# LineFollowTest.net
KiCad netlist of a schematic drawn in EAGLE
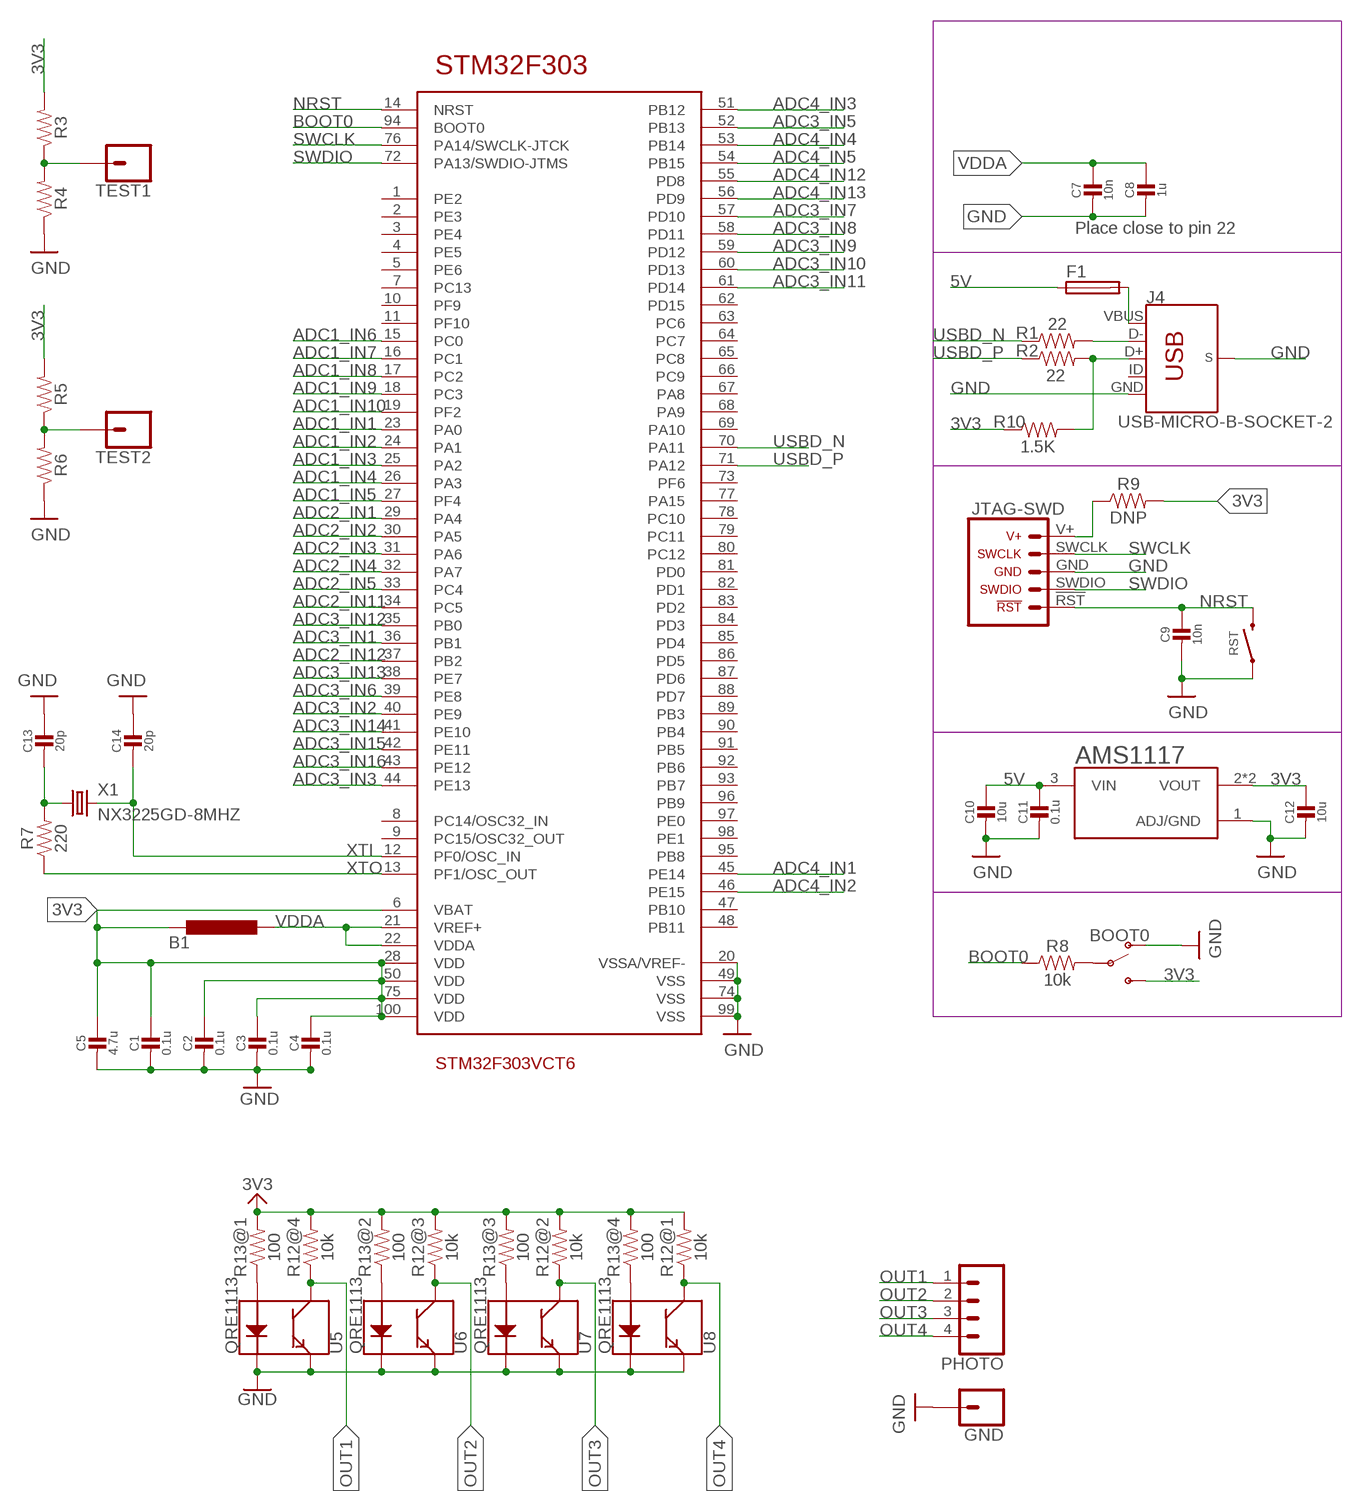
[diagram p0: schematic, sheet 1]
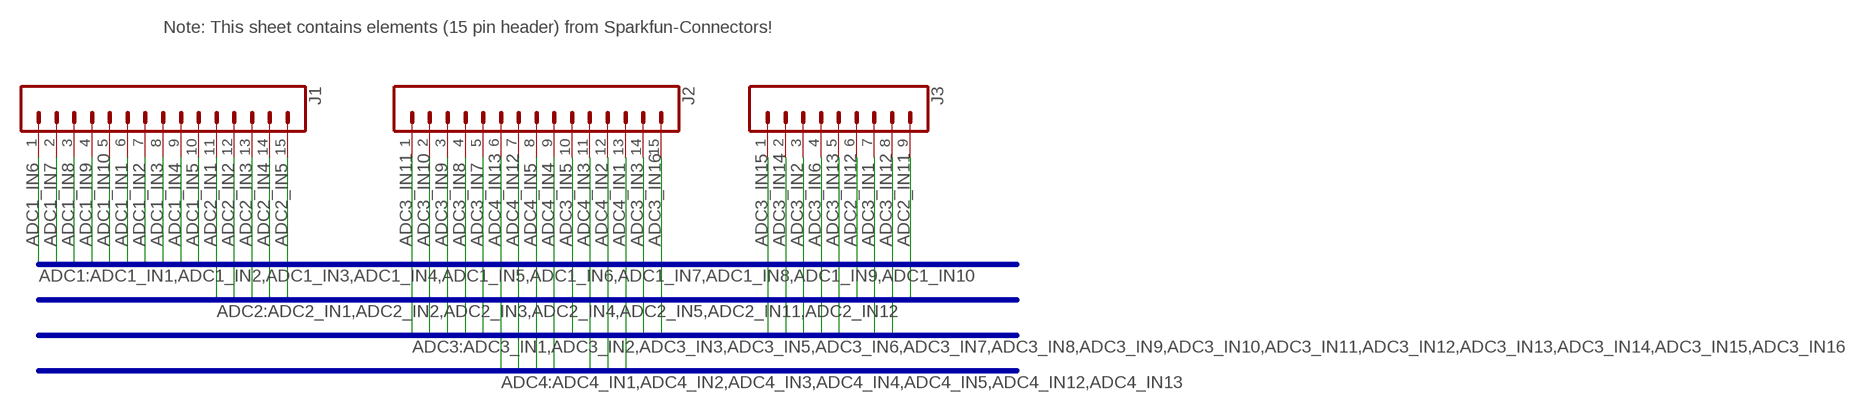
[diagram p1: schematic, sheet 2]
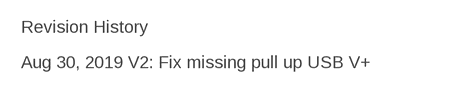
[diagram p2: schematic, sheet 3]

(export (version "E")
  (design (tool "Eeschema 10.0.6"))
  (components
    (comp (ref "J1")
      (value "CONN_15")
      (footprint "eagle-import:1X15")
      (libsource (lib "eagle-import") (part "CONN_15"))
    )
    (comp (ref "J2")
      (value "CONN_15")
      (footprint "eagle-import:1X15")
      (libsource (lib "eagle-import") (part "CONN_15"))
    )
    (comp (ref "J3")
      (value "CONN_09")
      (footprint "eagle-import:1X09")
      (libsource (lib "eagle-import") (part "CONN_09"))
    )
    (comp (ref "AMS1117")
      (value "3.3V")
      (footprint "eagle-import:SOT89")
      (libsource (lib "eagle-import") (part "VREG_AMS1117SMALL"))
    )
    (comp (ref "B1")
      (value "BEAD-0603")
      (footprint "eagle-import:0603")
      (libsource (lib "eagle-import") (part "BEAD-0603"))
    )
    (comp (ref "BOOT0")
      (value "SWITCH_SPDT_SLIDE")
      (footprint "eagle-import:SWITCH_SPDT_PTH_11.6X4.0MM")
      (libsource (lib "eagle-import") (part "SWITCH_SPDT_SLIDE"))
    )
    (comp (ref "C1")
      (value "0.1u")
      (footprint "eagle-import:CAP_0603")
      (libsource (lib "eagle-import") (part "CAP_CERAMIC_0603"))
    )
    (comp (ref "C2")
      (value "0.1u")
      (footprint "eagle-import:CAP_0603")
      (libsource (lib "eagle-import") (part "CAP_CERAMIC_0603"))
    )
    (comp (ref "C3")
      (value "0.1u")
      (footprint "eagle-import:CAP_0603")
      (libsource (lib "eagle-import") (part "CAP_CERAMIC_0603"))
    )
    (comp (ref "C4")
      (value "0.1u")
      (footprint "eagle-import:CAP_0603")
      (libsource (lib "eagle-import") (part "CAP_CERAMIC_0603"))
    )
    (comp (ref "C5")
      (value "4.7u")
      (footprint "eagle-import:CAP_0603")
      (libsource (lib "eagle-import") (part "CAP_CERAMIC_0603"))
    )
    (comp (ref "C7")
      (value "10n")
      (footprint "eagle-import:CAP_0603")
      (libsource (lib "eagle-import") (part "CAP_CERAMIC_0603"))
    )
    (comp (ref "C8")
      (value "1u")
      (footprint "eagle-import:CAP_0603")
      (libsource (lib "eagle-import") (part "CAP_CERAMIC_0603"))
    )
    (comp (ref "C9")
      (value "10n")
      (footprint "eagle-import:CAP_0603")
      (libsource (lib "eagle-import") (part "CAP_CERAMIC_0603"))
    )
    (comp (ref "C10")
      (value "10u")
      (footprint "eagle-import:CAP_0603")
      (libsource (lib "eagle-import") (part "CAP_CERAMIC_0603"))
    )
    (comp (ref "C11")
      (value "0.1u")
      (footprint "eagle-import:CAP_0603")
      (libsource (lib "eagle-import") (part "CAP_CERAMIC_0603"))
    )
    (comp (ref "C12")
      (value "10u")
      (footprint "eagle-import:CAP_0603")
      (libsource (lib "eagle-import") (part "CAP_CERAMIC_0603"))
    )
    (comp (ref "C13")
      (value "20p")
      (footprint "eagle-import:CAP_0603")
      (libsource (lib "eagle-import") (part "CAP_CERAMIC_0603"))
    )
    (comp (ref "C14")
      (value "20p")
      (footprint "eagle-import:CAP_0603")
      (libsource (lib "eagle-import") (part "CAP_CERAMIC_0603"))
    )
    (comp (ref "F1")
      (value "FUSE-1206")
      (footprint "eagle-import:1206")
      (libsource (lib "eagle-import") (part "FUSE-1206"))
    )
    (comp (ref "GND")
      (value "THD_01")
      (footprint "eagle-import:1X01")
      (libsource (lib "eagle-import") (part "THD_01"))
    )
    (comp (ref "J4")
      (value "USB-MICRO-B-SOCKET-2")
      (footprint "eagle-import:USB-MICRO-B-SOCKET-2")
      (libsource (lib "eagle-import") (part "USB-MICRO-B-SOCKET-2"))
    )
    (comp (ref "PHOTO")
      (value "CONN_04PTH")
      (footprint "eagle-import:1X04")
      (libsource (lib "eagle-import") (part "CONN_04PTH"))
    )
    (comp (ref "R1")
      (value "22")
      (footprint "eagle-import:0603")
      (libsource (lib "eagle-import") (part "RESISTOR0603"))
    )
    (comp (ref "R2")
      (value "22")
      (footprint "eagle-import:0603")
      (libsource (lib "eagle-import") (part "RESISTOR0603"))
    )
    (comp (ref "R3")
      (value "RESISTOR0603")
      (footprint "eagle-import:0603")
      (libsource (lib "eagle-import") (part "RESISTOR0603"))
    )
    (comp (ref "R4")
      (value "RESISTOR0603")
      (footprint "eagle-import:0603")
      (libsource (lib "eagle-import") (part "RESISTOR0603"))
    )
    (comp (ref "R5")
      (value "RESISTOR0603")
      (footprint "eagle-import:0603")
      (libsource (lib "eagle-import") (part "RESISTOR0603"))
    )
    (comp (ref "R6")
      (value "RESISTOR0603")
      (footprint "eagle-import:0603")
      (libsource (lib "eagle-import") (part "RESISTOR0603"))
    )
    (comp (ref "R7")
      (value "220")
      (footprint "eagle-import:0603")
      (libsource (lib "eagle-import") (part "RESISTOR0603"))
    )
    (comp (ref "R8")
      (value "10k")
      (footprint "eagle-import:0603")
      (libsource (lib "eagle-import") (part "RESISTOR0603"))
    )
    (comp (ref "R9")
      (value "DNP")
      (footprint "eagle-import:0603")
      (libsource (lib "eagle-import") (part "RESISTOR0603"))
    )
    (comp (ref "R10")
      (value "1.5K")
      (footprint "eagle-import:0603")
      (libsource (lib "eagle-import") (part "RESISTOR0603"))
    )
    (comp (ref "R12")
      (value "10k")
      (footprint "eagle-import:RESCAF80P320X160X60-8N")
      (libsource (lib "eagle-import") (part "RESISTOR_ARRAY_1206_SEPARATE"))
    )
    (comp (ref "R13")
      (value "100")
      (footprint "eagle-import:RESCAF80P320X160X60-8N")
      (libsource (lib "eagle-import") (part "RESISTOR_ARRAY_1206_SEPARATE"))
    )
    (comp (ref "RST")
      (value "PUSHBUTTON")
      (footprint "eagle-import:TACTILE_SWITCH_SMD_6.0X3.5MM")
      (libsource (lib "eagle-import") (part "PUSHBUTTON"))
    )
    (comp (ref "STM32F303")
      (value "STM32F303VCT6")
      (footprint "eagle-import:LQFP-100")
      (libsource (lib "eagle-import") (part "STM32F303VCT6"))
    )
    (comp (ref "TEST1")
      (value "THD_01")
      (footprint "eagle-import:1X01")
      (libsource (lib "eagle-import") (part "THD_01"))
    )
    (comp (ref "TEST2")
      (value "THD_01")
      (footprint "eagle-import:1X01")
      (libsource (lib "eagle-import") (part "THD_01"))
    )
    (comp (ref "U$3")
      (value "JTAG-SWD")
      (footprint "eagle-import:JTAG_SWD")
      (libsource (lib "eagle-import") (part "JTAG-SWD"))
    )
    (comp (ref "U5")
      (value "QRE1113")
      (footprint "eagle-import:QRE1113-W")
      (libsource (lib "eagle-import") (part "QRE1113SMD-W"))
    )
    (comp (ref "U6")
      (value "QRE1113")
      (footprint "eagle-import:QRE1113-W")
      (libsource (lib "eagle-import") (part "QRE1113SMD-W"))
    )
    (comp (ref "U7")
      (value "QRE1113")
      (footprint "eagle-import:QRE1113-W")
      (libsource (lib "eagle-import") (part "QRE1113SMD-W"))
    )
    (comp (ref "U8")
      (value "QRE1113")
      (footprint "eagle-import:QRE1113-W")
      (libsource (lib "eagle-import") (part "QRE1113SMD-W"))
    )
    (comp (ref "X1")
      (value "NX3225GD-8MHZ")
      (footprint "eagle-import:XTAL-SMD-3225")
      (libsource (lib "eagle-import") (part "XTAL-SMD-3225"))
    )
  )
  (nets
    (net (code "9") (name "3V3") (class "Default")
      (node (ref "AMS1117") (pin "2") (pinfunction "VOUT_2") (pintype "output"))
      (node (ref "AMS1117") (pin "2@1") (pinfunction "VOUT_2@1") (pintype "output"))
      (node (ref "B1") (pin "1") (pinfunction "P$1_1") (pintype "passive"))
      (node (ref "BOOT0") (pin "3") (pinfunction "S_3") (pintype "passive"))
      (node (ref "C1") (pin "1") (pinfunction "1_1") (pintype "passive"))
      (node (ref "C12") (pin "1") (pinfunction "1_1") (pintype "passive"))
      (node (ref "C2") (pin "1") (pinfunction "1_1") (pintype "passive"))
      (node (ref "C3") (pin "1") (pinfunction "1_1") (pintype "passive"))
      (node (ref "C4") (pin "1") (pinfunction "1_1") (pintype "passive"))
      (node (ref "C5") (pin "1") (pinfunction "1_1") (pintype "passive"))
      (node (ref "R10") (pin "1") (pinfunction "1_1") (pintype "passive"))
      (node (ref "R12") (pin "5") (pinfunction "2_5") (pintype "passive"))
      (node (ref "R12") (pin "6") (pinfunction "2_6") (pintype "passive"))
      (node (ref "R12") (pin "7") (pinfunction "2_7") (pintype "passive"))
      (node (ref "R12") (pin "8") (pinfunction "2_8") (pintype "passive"))
      (node (ref "R13") (pin "5") (pinfunction "2_5") (pintype "passive"))
      (node (ref "R13") (pin "6") (pinfunction "2_6") (pintype "passive"))
      (node (ref "R13") (pin "7") (pinfunction "2_7") (pintype "passive"))
      (node (ref "R13") (pin "8") (pinfunction "2_8") (pintype "passive"))
      (node (ref "R3") (pin "2") (pinfunction "2_2") (pintype "passive"))
      (node (ref "R5") (pin "2") (pinfunction "2_2") (pintype "passive"))
      (node (ref "R9") (pin "2") (pinfunction "2_2") (pintype "passive"))
      (node (ref "STM32F303") (pin "100") (pinfunction "VDD_100") (pintype "bidirectional"))
      (node (ref "STM32F303") (pin "28") (pinfunction "VDD_28") (pintype "bidirectional"))
      (node (ref "STM32F303") (pin "50") (pinfunction "VDD_50") (pintype "bidirectional"))
      (node (ref "STM32F303") (pin "6") (pinfunction "VBAT_6") (pintype "bidirectional"))
      (node (ref "STM32F303") (pin "75") (pinfunction "VDD_75") (pintype "bidirectional"))
    )
    (net (code "10") (name "5V") (class "Default")
      (node (ref "AMS1117") (pin "3") (pinfunction "VIN_3") (pintype "input"))
      (node (ref "C10") (pin "1") (pinfunction "1_1") (pintype "passive"))
      (node (ref "C11") (pin "1") (pinfunction "1_1") (pintype "passive"))
      (node (ref "F1") (pin "1") (pinfunction "1_1") (pintype "passive"))
    )
    (net (code "11") (name "ADC1_IN1") (class "Default")
      (node (ref "J1") (pin "6") (pinfunction "6_6") (pintype "passive"))
      (node (ref "STM32F303") (pin "23") (pinfunction "PA0_23") (pintype "bidirectional"))
    )
    (net (code "12") (name "ADC1_IN2") (class "Default")
      (node (ref "J1") (pin "7") (pinfunction "7_7") (pintype "passive"))
      (node (ref "STM32F303") (pin "24") (pinfunction "PA1_24") (pintype "bidirectional"))
    )
    (net (code "13") (name "ADC1_IN3") (class "Default")
      (node (ref "J1") (pin "8") (pinfunction "8_8") (pintype "passive"))
      (node (ref "STM32F303") (pin "25") (pinfunction "PA2_25") (pintype "bidirectional"))
    )
    (net (code "14") (name "ADC1_IN4") (class "Default")
      (node (ref "J1") (pin "9") (pinfunction "9_9") (pintype "passive"))
      (node (ref "STM32F303") (pin "26") (pinfunction "PA3_26") (pintype "bidirectional"))
    )
    (net (code "15") (name "ADC1_IN5") (class "Default")
      (node (ref "J1") (pin "10") (pinfunction "10_10") (pintype "passive"))
      (node (ref "STM32F303") (pin "27") (pinfunction "PF4_27") (pintype "bidirectional"))
    )
    (net (code "16") (name "ADC1_IN6") (class "Default")
      (node (ref "J1") (pin "1") (pinfunction "1_1") (pintype "passive"))
      (node (ref "STM32F303") (pin "15") (pinfunction "PC0_15") (pintype "bidirectional"))
    )
    (net (code "17") (name "ADC1_IN7") (class "Default")
      (node (ref "J1") (pin "2") (pinfunction "2_2") (pintype "passive"))
      (node (ref "STM32F303") (pin "16") (pinfunction "PC1_16") (pintype "bidirectional"))
    )
    (net (code "18") (name "ADC1_IN8") (class "Default")
      (node (ref "J1") (pin "3") (pinfunction "3_3") (pintype "passive"))
      (node (ref "STM32F303") (pin "17") (pinfunction "PC2_17") (pintype "bidirectional"))
    )
    (net (code "19") (name "ADC1_IN9") (class "Default")
      (node (ref "J1") (pin "4") (pinfunction "4_4") (pintype "passive"))
      (node (ref "STM32F303") (pin "18") (pinfunction "PC3_18") (pintype "bidirectional"))
    )
    (net (code "20") (name "ADC1_IN10") (class "Default")
      (node (ref "J1") (pin "5") (pinfunction "5_5") (pintype "passive"))
      (node (ref "STM32F303") (pin "19") (pinfunction "PF2_19") (pintype "bidirectional"))
    )
    (net (code "21") (name "ADC2_IN1") (class "Default")
      (node (ref "J1") (pin "11") (pinfunction "11_11") (pintype "passive"))
      (node (ref "STM32F303") (pin "29") (pinfunction "PA4_29") (pintype "bidirectional"))
    )
    (net (code "22") (name "ADC2_IN2") (class "Default")
      (node (ref "J1") (pin "12") (pinfunction "12_12") (pintype "passive"))
      (node (ref "STM32F303") (pin "30") (pinfunction "PA5_30") (pintype "bidirectional"))
    )
    (net (code "23") (name "ADC2_IN3") (class "Default")
      (node (ref "J1") (pin "13") (pinfunction "13_13") (pintype "passive"))
      (node (ref "STM32F303") (pin "31") (pinfunction "PA6_31") (pintype "bidirectional"))
    )
    (net (code "24") (name "ADC2_IN4") (class "Default")
      (node (ref "J1") (pin "14") (pinfunction "14_14") (pintype "passive"))
      (node (ref "STM32F303") (pin "32") (pinfunction "PA7_32") (pintype "bidirectional"))
    )
    (net (code "25") (name "ADC2_IN5") (class "Default")
      (node (ref "J1") (pin "15") (pinfunction "15_15") (pintype "passive"))
      (node (ref "STM32F303") (pin "33") (pinfunction "PC4_33") (pintype "bidirectional"))
    )
    (net (code "26") (name "ADC2_IN11") (class "Default")
      (node (ref "J3") (pin "9") (pinfunction "9_9") (pintype "passive"))
      (node (ref "STM32F303") (pin "34") (pinfunction "PC5_34") (pintype "bidirectional"))
    )
    (net (code "27") (name "ADC2_IN12") (class "Default")
      (node (ref "J3") (pin "6") (pinfunction "6_6") (pintype "passive"))
      (node (ref "STM32F303") (pin "37") (pinfunction "PB2_37") (pintype "bidirectional"))
    )
    (net (code "28") (name "ADC3_IN1") (class "Default")
      (node (ref "J3") (pin "7") (pinfunction "7_7") (pintype "passive"))
      (node (ref "STM32F303") (pin "36") (pinfunction "PB1_36") (pintype "bidirectional"))
    )
    (net (code "29") (name "ADC3_IN2") (class "Default")
      (node (ref "J3") (pin "3") (pinfunction "3_3") (pintype "passive"))
      (node (ref "STM32F303") (pin "40") (pinfunction "PE9_40") (pintype "bidirectional"))
    )
    (net (code "30") (name "ADC3_IN3") (class "Default")
      (node (ref "J2") (pin "14") (pinfunction "14_14") (pintype "passive"))
      (node (ref "STM32F303") (pin "44") (pinfunction "PE13_44") (pintype "bidirectional"))
    )
    (net (code "31") (name "ADC3_IN5") (class "Default")
      (node (ref "J2") (pin "10") (pinfunction "10_10") (pintype "passive"))
      (node (ref "STM32F303") (pin "52") (pinfunction "PB13_52") (pintype "bidirectional"))
    )
    (net (code "32") (name "ADC3_IN6") (class "Default")
      (node (ref "J3") (pin "4") (pinfunction "4_4") (pintype "passive"))
      (node (ref "STM32F303") (pin "39") (pinfunction "PE8_39") (pintype "bidirectional"))
    )
    (net (code "33") (name "ADC3_IN7") (class "Default")
      (node (ref "J2") (pin "5") (pinfunction "5_5") (pintype "passive"))
      (node (ref "STM32F303") (pin "57") (pinfunction "PD10_57") (pintype "bidirectional"))
    )
    (net (code "34") (name "ADC3_IN8") (class "Default")
      (node (ref "J2") (pin "4") (pinfunction "4_4") (pintype "passive"))
      (node (ref "STM32F303") (pin "58") (pinfunction "PD11_58") (pintype "bidirectional"))
    )
    (net (code "35") (name "ADC3_IN9") (class "Default")
      (node (ref "J2") (pin "3") (pinfunction "3_3") (pintype "passive"))
      (node (ref "STM32F303") (pin "59") (pinfunction "PD12_59") (pintype "bidirectional"))
    )
    (net (code "36") (name "ADC3_IN10") (class "Default")
      (node (ref "J2") (pin "2") (pinfunction "2_2") (pintype "passive"))
      (node (ref "STM32F303") (pin "60") (pinfunction "PD13_60") (pintype "bidirectional"))
    )
    (net (code "37") (name "ADC3_IN11") (class "Default")
      (node (ref "J2") (pin "1") (pinfunction "1_1") (pintype "passive"))
      (node (ref "STM32F303") (pin "61") (pinfunction "PD14_61") (pintype "bidirectional"))
    )
    (net (code "38") (name "ADC3_IN12") (class "Default")
      (node (ref "J3") (pin "8") (pinfunction "8_8") (pintype "passive"))
      (node (ref "STM32F303") (pin "35") (pinfunction "PB0_35") (pintype "bidirectional"))
    )
    (net (code "39") (name "ADC3_IN13") (class "Default")
      (node (ref "J3") (pin "5") (pinfunction "5_5") (pintype "passive"))
      (node (ref "STM32F303") (pin "38") (pinfunction "PE7_38") (pintype "bidirectional"))
    )
    (net (code "40") (name "ADC3_IN14") (class "Default")
      (node (ref "J3") (pin "2") (pinfunction "2_2") (pintype "passive"))
      (node (ref "STM32F303") (pin "41") (pinfunction "PE10_41") (pintype "bidirectional"))
    )
    (net (code "41") (name "ADC3_IN15") (class "Default")
      (node (ref "J3") (pin "1") (pinfunction "1_1") (pintype "passive"))
      (node (ref "STM32F303") (pin "42") (pinfunction "PE11_42") (pintype "bidirectional"))
    )
    (net (code "42") (name "ADC3_IN16") (class "Default")
      (node (ref "J2") (pin "15") (pinfunction "15_15") (pintype "passive"))
      (node (ref "STM32F303") (pin "43") (pinfunction "PE12_43") (pintype "bidirectional"))
    )
    (net (code "43") (name "ADC4_IN1") (class "Default")
      (node (ref "J2") (pin "13") (pinfunction "13_13") (pintype "passive"))
      (node (ref "STM32F303") (pin "45") (pinfunction "PE14_45") (pintype "bidirectional"))
    )
    (net (code "44") (name "ADC4_IN2") (class "Default")
      (node (ref "J2") (pin "12") (pinfunction "12_12") (pintype "passive"))
      (node (ref "STM32F303") (pin "46") (pinfunction "PE15_46") (pintype "bidirectional"))
    )
    (net (code "45") (name "ADC4_IN3") (class "Default")
      (node (ref "J2") (pin "11") (pinfunction "11_11") (pintype "passive"))
      (node (ref "STM32F303") (pin "51") (pinfunction "PB12_51") (pintype "bidirectional"))
    )
    (net (code "46") (name "ADC4_IN4") (class "Default")
      (node (ref "J2") (pin "9") (pinfunction "9_9") (pintype "passive"))
      (node (ref "STM32F303") (pin "53") (pinfunction "PB14_53") (pintype "bidirectional"))
    )
    (net (code "47") (name "ADC4_IN5") (class "Default")
      (node (ref "J2") (pin "8") (pinfunction "8_8") (pintype "passive"))
      (node (ref "STM32F303") (pin "54") (pinfunction "PB15_54") (pintype "bidirectional"))
    )
    (net (code "48") (name "ADC4_IN12") (class "Default")
      (node (ref "J2") (pin "7") (pinfunction "7_7") (pintype "passive"))
      (node (ref "STM32F303") (pin "55") (pinfunction "PD8_55") (pintype "bidirectional"))
    )
    (net (code "49") (name "ADC4_IN13") (class "Default")
      (node (ref "J2") (pin "6") (pinfunction "6_6") (pintype "passive"))
      (node (ref "STM32F303") (pin "56") (pinfunction "PD9_56") (pintype "bidirectional"))
    )
    (net (code "50") (name "BOOT0") (class "Default")
      (node (ref "R8") (pin "1") (pinfunction "1_1") (pintype "passive"))
      (node (ref "STM32F303") (pin "94") (pinfunction "BOOT0_94") (pintype "bidirectional"))
    )
    (net (code "51") (name "GND") (class "Default")
      (node (ref "AMS1117") (pin "1") (pinfunction "ADJ/GND_1") (pintype "power_in"))
      (node (ref "BOOT0") (pin "1") (pinfunction "O_1") (pintype "passive"))
      (node (ref "C1") (pin "2") (pinfunction "2_2") (pintype "passive"))
      (node (ref "C10") (pin "2") (pinfunction "2_2") (pintype "passive"))
      (node (ref "C11") (pin "2") (pinfunction "2_2") (pintype "passive"))
      (node (ref "C12") (pin "2") (pinfunction "2_2") (pintype "passive"))
      (node (ref "C13") (pin "1") (pinfunction "1_1") (pintype "passive"))
      (node (ref "C14") (pin "1") (pinfunction "1_1") (pintype "passive"))
      (node (ref "C2") (pin "2") (pinfunction "2_2") (pintype "passive"))
      (node (ref "C3") (pin "2") (pinfunction "2_2") (pintype "passive"))
      (node (ref "C4") (pin "2") (pinfunction "2_2") (pintype "passive"))
      (node (ref "C5") (pin "2") (pinfunction "2_2") (pintype "passive"))
      (node (ref "C7") (pin "2") (pinfunction "2_2") (pintype "passive"))
      (node (ref "C8") (pin "2") (pinfunction "2_2") (pintype "passive"))
      (node (ref "C9") (pin "2") (pinfunction "2_2") (pintype "passive"))
      (node (ref "GND") (pin "1") (pinfunction "1_1") (pintype "passive"))
      (node (ref "J4") (pin "GND") (pinfunction "GND_GND") (pintype "power_in"))
      (node (ref "J4") (pin "S1") (pinfunction "SHIELD_S1") (pintype "bidirectional"))
      (node (ref "J4") (pin "S2") (pinfunction "SHIELD_S2") (pintype "bidirectional"))
      (node (ref "J4") (pin "S3") (pinfunction "SHIELD_S3") (pintype "bidirectional"))
      (node (ref "J4") (pin "S4") (pinfunction "SHIELD_S4") (pintype "bidirectional"))
      (node (ref "J4") (pin "S5") (pinfunction "SHIELD_S5") (pintype "bidirectional"))
      (node (ref "R4") (pin "1") (pinfunction "1_1") (pintype "passive"))
      (node (ref "R6") (pin "1") (pinfunction "1_1") (pintype "passive"))
      (node (ref "RST") (pin "1") (pinfunction "1_1") (pintype "passive"))
      (node (ref "STM32F303") (pin "20") (pinfunction "VSSA/VREF-_20") (pintype "bidirectional"))
      (node (ref "STM32F303") (pin "49") (pinfunction "VSS_49") (pintype "bidirectional"))
      (node (ref "STM32F303") (pin "74") (pinfunction "VSS_74") (pintype "bidirectional"))
      (node (ref "STM32F303") (pin "99") (pinfunction "VSS_99") (pintype "bidirectional"))
      (node (ref "U$3") (pin "GND") (pinfunction "GND_GND") (pintype "passive"))
      (node (ref "U5") (pin "2") (pinfunction "K_2") (pintype "bidirectional"))
      (node (ref "U5") (pin "4") (pinfunction "E_4") (pintype "bidirectional"))
      (node (ref "U6") (pin "2") (pinfunction "K_2") (pintype "bidirectional"))
      (node (ref "U6") (pin "4") (pinfunction "E_4") (pintype "bidirectional"))
      (node (ref "U7") (pin "2") (pinfunction "K_2") (pintype "bidirectional"))
      (node (ref "U7") (pin "4") (pinfunction "E_4") (pintype "bidirectional"))
      (node (ref "U8") (pin "2") (pinfunction "K_2") (pintype "bidirectional"))
      (node (ref "U8") (pin "4") (pinfunction "E_4") (pintype "bidirectional"))
    )
    (net (code "52") (name "NRST") (class "Default")
      (node (ref "C9") (pin "1") (pinfunction "1_1") (pintype "passive"))
      (node (ref "RST") (pin "2") (pinfunction "2_2") (pintype "passive"))
      (node (ref "STM32F303") (pin "14") (pinfunction "NRST_14") (pintype "bidirectional"))
      (node (ref "U$3") (pin "!RST") (pinfunction "~{RST}_!RST") (pintype "passive"))
    )
    (net (code "53") (name "Net-(BOOT0-P)") (class "Default")
      (node (ref "BOOT0") (pin "2") (pinfunction "P_2") (pintype "passive"))
      (node (ref "R8") (pin "2") (pinfunction "2_2") (pintype "passive"))
    )
    (net (code "54") (name "Net-(C13-Pad2)") (class "Default")
      (node (ref "C13") (pin "2") (pinfunction "2_2") (pintype "passive"))
      (node (ref "R7") (pin "2") (pinfunction "2_2") (pintype "passive"))
      (node (ref "X1") (pin "1") (pinfunction "1_1") (pintype "passive"))
    )
    (net (code "55") (name "Net-(F1-Pad2)") (class "Default")
      (node (ref "F1") (pin "2") (pinfunction "2_2") (pintype "passive"))
      (node (ref "J4") (pin "VBUS") (pinfunction "VBUS_VBUS") (pintype "power_in"))
    )
    (net (code "56") (name "Net-(J4-PadD+)") (class "Default")
      (node (ref "J4") (pin "D+") (pinfunction "D+_D+") (pintype "bidirectional"))
      (node (ref "R10") (pin "2") (pinfunction "2_2") (pintype "passive"))
      (node (ref "R2") (pin "2") (pinfunction "2_2") (pintype "passive"))
    )
    (net (code "57") (name "Net-(J4-PadD-)") (class "Default")
      (node (ref "J4") (pin "D-") (pinfunction "D-_D-") (pintype "bidirectional"))
      (node (ref "R1") (pin "2") (pinfunction "2_2") (pintype "passive"))
    )
    (net (code "58") (name "Net-(R3-Pad1)") (class "Default")
      (node (ref "R3") (pin "1") (pinfunction "1_1") (pintype "passive"))
      (node (ref "R4") (pin "2") (pinfunction "2_2") (pintype "passive"))
      (node (ref "TEST1") (pin "1") (pinfunction "1_1") (pintype "passive"))
    )
    (net (code "59") (name "Net-(R5-Pad1)") (class "Default")
      (node (ref "R5") (pin "1") (pinfunction "1_1") (pintype "passive"))
      (node (ref "R6") (pin "2") (pinfunction "2_2") (pintype "passive"))
      (node (ref "TEST2") (pin "1") (pinfunction "1_1") (pintype "passive"))
    )
    (net (code "60") (name "Net-(R9-Pad1)") (class "Default")
      (node (ref "R9") (pin "1") (pinfunction "1_1") (pintype "passive"))
      (node (ref "U$3") (pin "V+") (pinfunction "V+_V+") (pintype "passive"))
    )
    (net (code "61") (name "Net-(R13B-1)") (class "Default")
      (node (ref "R13") (pin "2") (pinfunction "1_2") (pintype "passive"))
      (node (ref "U6") (pin "1") (pinfunction "A_1") (pintype "bidirectional"))
    )
    (net (code "62") (name "Net-(R13C-1)") (class "Default")
      (node (ref "R13") (pin "3") (pinfunction "1_3") (pintype "passive"))
      (node (ref "U7") (pin "1") (pinfunction "A_1") (pintype "bidirectional"))
    )
    (net (code "63") (name "Net-(R13D-1)") (class "Default")
      (node (ref "R13") (pin "4") (pinfunction "1_4") (pintype "passive"))
      (node (ref "U8") (pin "1") (pinfunction "A_1") (pintype "bidirectional"))
    )
    (net (code "64") (name "Net-(U5-A)") (class "Default")
      (node (ref "R13") (pin "1") (pinfunction "1_1") (pintype "passive"))
      (node (ref "U5") (pin "1") (pinfunction "A_1") (pintype "bidirectional"))
    )
    (net (code "65") (name "OUT1") (class "Default")
      (node (ref "PHOTO") (pin "1") (pinfunction "1_1") (pintype "passive"))
      (node (ref "R12") (pin "4") (pinfunction "1_4") (pintype "passive"))
      (node (ref "U5") (pin "3") (pinfunction "C_3") (pintype "bidirectional"))
    )
    (net (code "66") (name "OUT2") (class "Default")
      (node (ref "PHOTO") (pin "2") (pinfunction "2_2") (pintype "passive"))
      (node (ref "R12") (pin "3") (pinfunction "1_3") (pintype "passive"))
      (node (ref "U6") (pin "3") (pinfunction "C_3") (pintype "bidirectional"))
    )
    (net (code "67") (name "OUT3") (class "Default")
      (node (ref "PHOTO") (pin "3") (pinfunction "3_3") (pintype "passive"))
      (node (ref "R12") (pin "2") (pinfunction "1_2") (pintype "passive"))
      (node (ref "U7") (pin "3") (pinfunction "C_3") (pintype "bidirectional"))
    )
    (net (code "68") (name "OUT4") (class "Default")
      (node (ref "PHOTO") (pin "4") (pinfunction "4_4") (pintype "passive"))
      (node (ref "R12") (pin "1") (pinfunction "1_1") (pintype "passive"))
      (node (ref "U8") (pin "3") (pinfunction "C_3") (pintype "bidirectional"))
    )
    (net (code "69") (name "SWCLK") (class "Default")
      (node (ref "STM32F303") (pin "76") (pinfunction "PA14/SWCLK-JTCK_76") (pintype "bidirectional"))
      (node (ref "U$3") (pin "SWCLK") (pinfunction "SWCLK_SWCLK") (pintype "passive"))
    )
    (net (code "70") (name "SWDIO") (class "Default")
      (node (ref "STM32F303") (pin "72") (pinfunction "PA13/SWDIO-JTMS_72") (pintype "bidirectional"))
      (node (ref "U$3") (pin "SWDIO") (pinfunction "SWDIO_SWDIO") (pintype "passive"))
    )
    (net (code "71") (name "USBD_N") (class "Default")
      (node (ref "R1") (pin "1") (pinfunction "1_1") (pintype "passive"))
      (node (ref "STM32F303") (pin "70") (pinfunction "PA11_70") (pintype "bidirectional"))
    )
    (net (code "72") (name "USBD_P") (class "Default")
      (node (ref "R2") (pin "1") (pinfunction "1_1") (pintype "passive"))
      (node (ref "STM32F303") (pin "71") (pinfunction "PA12_71") (pintype "bidirectional"))
    )
    (net (code "73") (name "VDDA") (class "Default")
      (node (ref "B1") (pin "2") (pinfunction "P$2_2") (pintype "passive"))
      (node (ref "C7") (pin "1") (pinfunction "1_1") (pintype "passive"))
      (node (ref "C8") (pin "1") (pinfunction "1_1") (pintype "passive"))
      (node (ref "STM32F303") (pin "21") (pinfunction "VREF+_21") (pintype "bidirectional"))
      (node (ref "STM32F303") (pin "22") (pinfunction "VDDA_22") (pintype "bidirectional"))
    )
    (net (code "74") (name "XTI") (class "Default")
      (node (ref "C14") (pin "2") (pinfunction "2_2") (pintype "passive"))
      (node (ref "STM32F303") (pin "12") (pinfunction "PF0/OSC_IN_12") (pintype "bidirectional"))
      (node (ref "X1") (pin "2") (pinfunction "2_2") (pintype "passive"))
    )
    (net (code "75") (name "XTO") (class "Default")
      (node (ref "R7") (pin "1") (pinfunction "1_1") (pintype "passive"))
      (node (ref "STM32F303") (pin "13") (pinfunction "PF1/OSC_OUT_13") (pintype "bidirectional"))
    )
    (net (code "76") (name "unconnected-(J4-PadID)") (class "Default")
      (node (ref "J4") (pin "ID") (pinfunction "ID_ID") (pintype "bidirectional"))
    )
    (net (code "77") (name "unconnected-(STM32F303-PA8-Pad67)") (class "Default")
      (node (ref "STM32F303") (pin "67") (pinfunction "PA8_67") (pintype "bidirectional"))
    )
    (net (code "78") (name "unconnected-(STM32F303-PA9-Pad68)") (class "Default")
      (node (ref "STM32F303") (pin "68") (pinfunction "PA9_68") (pintype "bidirectional"))
    )
    (net (code "79") (name "unconnected-(STM32F303-PA10-Pad69)") (class "Default")
      (node (ref "STM32F303") (pin "69") (pinfunction "PA10_69") (pintype "bidirectional"))
    )
    (net (code "80") (name "unconnected-(STM32F303-PA15-Pad77)") (class "Default")
      (node (ref "STM32F303") (pin "77") (pinfunction "PA15_77") (pintype "bidirectional"))
    )
    (net (code "81") (name "unconnected-(STM32F303-PB3-Pad89)") (class "Default")
      (node (ref "STM32F303") (pin "89") (pinfunction "PB3_89") (pintype "bidirectional"))
    )
    (net (code "82") (name "unconnected-(STM32F303-PB4-Pad90)") (class "Default")
      (node (ref "STM32F303") (pin "90") (pinfunction "PB4_90") (pintype "bidirectional"))
    )
    (net (code "83") (name "unconnected-(STM32F303-PB5-Pad91)") (class "Default")
      (node (ref "STM32F303") (pin "91") (pinfunction "PB5_91") (pintype "bidirectional"))
    )
    (net (code "84") (name "unconnected-(STM32F303-PB6-Pad92)") (class "Default")
      (node (ref "STM32F303") (pin "92") (pinfunction "PB6_92") (pintype "bidirectional"))
    )
    (net (code "85") (name "unconnected-(STM32F303-PB7-Pad93)") (class "Default")
      (node (ref "STM32F303") (pin "93") (pinfunction "PB7_93") (pintype "bidirectional"))
    )
    (net (code "86") (name "unconnected-(STM32F303-PB8-Pad95)") (class "Default")
      (node (ref "STM32F303") (pin "95") (pinfunction "PB8_95") (pintype "bidirectional"))
    )
    (net (code "87") (name "unconnected-(STM32F303-PB9-Pad96)") (class "Default")
      (node (ref "STM32F303") (pin "96") (pinfunction "PB9_96") (pintype "bidirectional"))
    )
    (net (code "88") (name "unconnected-(STM32F303-PB10-Pad47)") (class "Default")
      (node (ref "STM32F303") (pin "47") (pinfunction "PB10_47") (pintype "bidirectional"))
    )
    (net (code "89") (name "unconnected-(STM32F303-PB11-Pad48)") (class "Default")
      (node (ref "STM32F303") (pin "48") (pinfunction "PB11_48") (pintype "bidirectional"))
    )
    (net (code "90") (name "unconnected-(STM32F303-PC6-Pad63)") (class "Default")
      (node (ref "STM32F303") (pin "63") (pinfunction "PC6_63") (pintype "bidirectional"))
    )
    (net (code "91") (name "unconnected-(STM32F303-PC7-Pad64)") (class "Default")
      (node (ref "STM32F303") (pin "64") (pinfunction "PC7_64") (pintype "bidirectional"))
    )
    (net (code "92") (name "unconnected-(STM32F303-PC8-Pad65)") (class "Default")
      (node (ref "STM32F303") (pin "65") (pinfunction "PC8_65") (pintype "bidirectional"))
    )
    (net (code "93") (name "unconnected-(STM32F303-PC9-Pad66)") (class "Default")
      (node (ref "STM32F303") (pin "66") (pinfunction "PC9_66") (pintype "bidirectional"))
    )
    (net (code "94") (name "unconnected-(STM32F303-PC10-Pad78)") (class "Default")
      (node (ref "STM32F303") (pin "78") (pinfunction "PC10_78") (pintype "bidirectional"))
    )
    (net (code "95") (name "unconnected-(STM32F303-PC11-Pad79)") (class "Default")
      (node (ref "STM32F303") (pin "79") (pinfunction "PC11_79") (pintype "bidirectional"))
    )
    (net (code "96") (name "unconnected-(STM32F303-PC12-Pad80)") (class "Default")
      (node (ref "STM32F303") (pin "80") (pinfunction "PC12_80") (pintype "bidirectional"))
    )
    (net (code "97") (name "unconnected-(STM32F303-PC13-Pad7)") (class "Default")
      (node (ref "STM32F303") (pin "7") (pinfunction "PC13_7") (pintype "bidirectional"))
    )
    (net (code "98") (name "unconnected-(STM32F303-PC14{slash}OSC32_IN-Pad8)") (class "Default")
      (node (ref "STM32F303") (pin "8") (pinfunction "PC14/OSC32_IN_8") (pintype "bidirectional"))
    )
    (net (code "99") (name "unconnected-(STM32F303-PC15{slash}OSC32_OUT-Pad9)") (class "Default")
      (node (ref "STM32F303") (pin "9") (pinfunction "PC15/OSC32_OUT_9") (pintype "bidirectional"))
    )
    (net (code "100") (name "unconnected-(STM32F303-PD0-Pad81)") (class "Default")
      (node (ref "STM32F303") (pin "81") (pinfunction "PD0_81") (pintype "bidirectional"))
    )
    (net (code "101") (name "unconnected-(STM32F303-PD1-Pad82)") (class "Default")
      (node (ref "STM32F303") (pin "82") (pinfunction "PD1_82") (pintype "bidirectional"))
    )
    (net (code "102") (name "unconnected-(STM32F303-PD2-Pad83)") (class "Default")
      (node (ref "STM32F303") (pin "83") (pinfunction "PD2_83") (pintype "bidirectional"))
    )
    (net (code "103") (name "unconnected-(STM32F303-PD3-Pad84)") (class "Default")
      (node (ref "STM32F303") (pin "84") (pinfunction "PD3_84") (pintype "bidirectional"))
    )
    (net (code "104") (name "unconnected-(STM32F303-PD4-Pad85)") (class "Default")
      (node (ref "STM32F303") (pin "85") (pinfunction "PD4_85") (pintype "bidirectional"))
    )
    (net (code "105") (name "unconnected-(STM32F303-PD5-Pad86)") (class "Default")
      (node (ref "STM32F303") (pin "86") (pinfunction "PD5_86") (pintype "bidirectional"))
    )
    (net (code "106") (name "unconnected-(STM32F303-PD6-Pad87)") (class "Default")
      (node (ref "STM32F303") (pin "87") (pinfunction "PD6_87") (pintype "bidirectional"))
    )
    (net (code "107") (name "unconnected-(STM32F303-PD7-Pad88)") (class "Default")
      (node (ref "STM32F303") (pin "88") (pinfunction "PD7_88") (pintype "bidirectional"))
    )
    (net (code "108") (name "unconnected-(STM32F303-PD15-Pad62)") (class "Default")
      (node (ref "STM32F303") (pin "62") (pinfunction "PD15_62") (pintype "bidirectional"))
    )
    (net (code "109") (name "unconnected-(STM32F303-PE0-Pad97)") (class "Default")
      (node (ref "STM32F303") (pin "97") (pinfunction "PE0_97") (pintype "bidirectional"))
    )
    (net (code "110") (name "unconnected-(STM32F303-PE1-Pad98)") (class "Default")
      (node (ref "STM32F303") (pin "98") (pinfunction "PE1_98") (pintype "bidirectional"))
    )
    (net (code "111") (name "unconnected-(STM32F303-PE2-Pad1)") (class "Default")
      (node (ref "STM32F303") (pin "1") (pinfunction "PE2_1") (pintype "bidirectional"))
    )
    (net (code "112") (name "unconnected-(STM32F303-PE3-Pad2)") (class "Default")
      (node (ref "STM32F303") (pin "2") (pinfunction "PE3_2") (pintype "bidirectional"))
    )
    (net (code "113") (name "unconnected-(STM32F303-PE4-Pad3)") (class "Default")
      (node (ref "STM32F303") (pin "3") (pinfunction "PE4_3") (pintype "bidirectional"))
    )
    (net (code "114") (name "unconnected-(STM32F303-PE5-Pad4)") (class "Default")
      (node (ref "STM32F303") (pin "4") (pinfunction "PE5_4") (pintype "bidirectional"))
    )
    (net (code "115") (name "unconnected-(STM32F303-PE6-Pad5)") (class "Default")
      (node (ref "STM32F303") (pin "5") (pinfunction "PE6_5") (pintype "bidirectional"))
    )
    (net (code "116") (name "unconnected-(STM32F303-PF6-Pad73)") (class "Default")
      (node (ref "STM32F303") (pin "73") (pinfunction "PF6_73") (pintype "bidirectional"))
    )
    (net (code "117") (name "unconnected-(STM32F303-PF9-Pad10)") (class "Default")
      (node (ref "STM32F303") (pin "10") (pinfunction "PF9_10") (pintype "bidirectional"))
    )
    (net (code "118") (name "unconnected-(STM32F303-PF10-Pad11)") (class "Default")
      (node (ref "STM32F303") (pin "11") (pinfunction "PF10_11") (pintype "bidirectional"))
    )
  )
)
